# HeatpumpMonitor.net
KiCad netlist of a schematic drawn in EAGLE
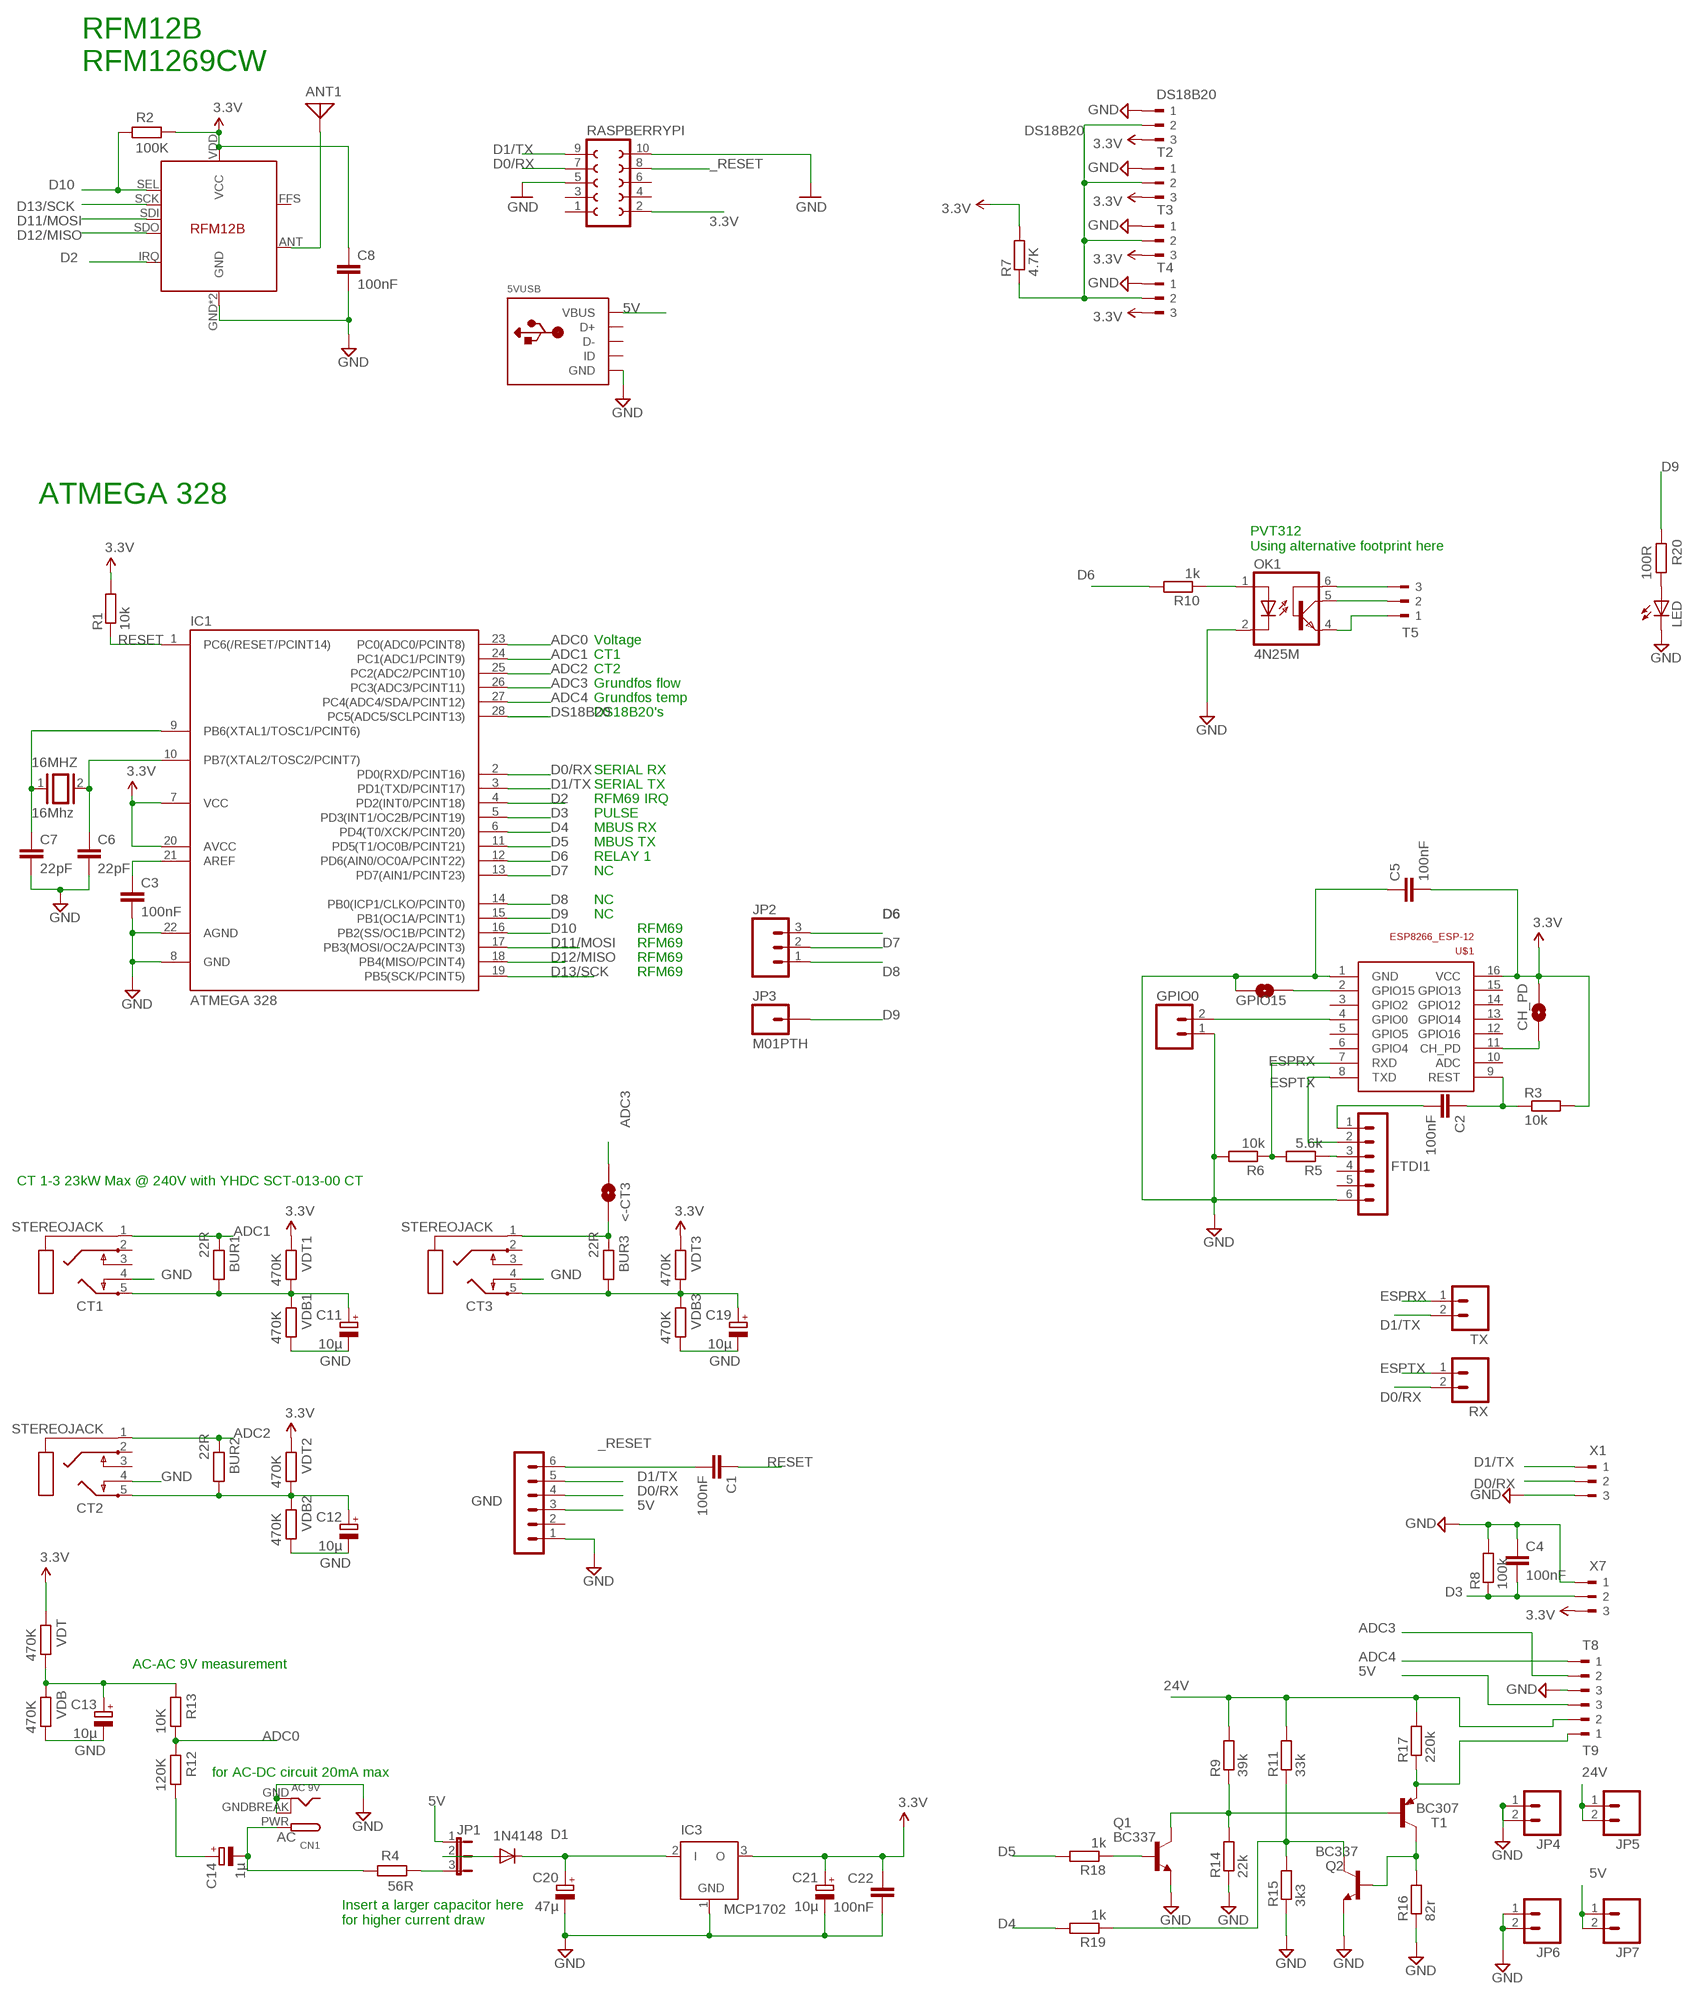
[diagram p0: schematic, sheet 1]

(export (version "E")
  (design (tool "Eeschema 10.0.6"))
  (components
    (comp (ref "5VUSB")
      (value "USBMOLEX")
      (footprint "eagle-import:USB-MINIB-THM-MOLEX")
      (libsource (lib "eagle-import") (part "USBMOLEX"))
    )
    (comp (ref "16MHZ")
      (value "16Mhz")
      (footprint "eagle-import:QS")
      (libsource (lib "eagle-import") (part "XTAL/S"))
    )
    (comp (ref "<-CT3")
      (value "SOLDERJUMPERNO")
      (footprint "eagle-import:SJ_2S-NO")
      (libsource (lib "eagle-import") (part "SOLDERJUMPERNO"))
    )
    (comp (ref "ANT1")
      (value "ANTENNA")
      (footprint "eagle-import:PAD-01")
      (libsource (lib "eagle-import") (part "ANTENNA"))
    )
    (comp (ref "BUR1")
      (value "22R")
      (footprint "eagle-import:0204_7")
      (libsource (lib "eagle-import") (part "R-EU_0204/7"))
    )
    (comp (ref "BUR2")
      (value "22R")
      (footprint "eagle-import:0204_7")
      (libsource (lib "eagle-import") (part "R-EU_0204/7"))
    )
    (comp (ref "BUR3")
      (value "22R")
      (footprint "eagle-import:0204_7")
      (libsource (lib "eagle-import") (part "R-EU_0204/7"))
    )
    (comp (ref "C1")
      (value "100nF")
      (footprint "eagle-import:C025-024X044")
      (libsource (lib "eagle-import") (part "C-EU025-024X044"))
    )
    (comp (ref "C2")
      (value "100nF")
      (footprint "eagle-import:C025-024X044")
      (libsource (lib "eagle-import") (part "C-EU025-024X044"))
    )
    (comp (ref "C3")
      (value "100nF")
      (footprint "eagle-import:C025-024X044")
      (libsource (lib "eagle-import") (part "C-EU025-024X044"))
    )
    (comp (ref "C4")
      (value "100nF")
      (footprint "eagle-import:C025-024X044")
      (libsource (lib "eagle-import") (part "C-EU025-024X044"))
    )
    (comp (ref "C5")
      (value "100nF")
      (footprint "eagle-import:C025-024X044")
      (libsource (lib "eagle-import") (part "C-EU025-024X044"))
    )
    (comp (ref "C6")
      (value "22pF")
      (footprint "eagle-import:C2.5-2")
      (libsource (lib "eagle-import") (part "C2.5/2"))
    )
    (comp (ref "C7")
      (value "22pF")
      (footprint "eagle-import:C2.5-2")
      (libsource (lib "eagle-import") (part "C2.5/2"))
    )
    (comp (ref "C8")
      (value "100nF")
      (footprint "eagle-import:C025-024X044")
      (libsource (lib "eagle-import") (part "C-EU025-024X044"))
    )
    (comp (ref "C11")
      (value "10µ")
      (footprint "eagle-import:E1,8-4")
      (libsource (lib "eagle-import") (part "CPOL-EUE1.8-4"))
    )
    (comp (ref "C12")
      (value "10µ")
      (footprint "eagle-import:E1,8-4")
      (libsource (lib "eagle-import") (part "CPOL-EUE1.8-4"))
    )
    (comp (ref "C13")
      (value "10µ")
      (footprint "eagle-import:E1,8-4")
      (libsource (lib "eagle-import") (part "CPOL-EUE1.8-4"))
    )
    (comp (ref "C14")
      (value "1µ")
      (footprint "eagle-import:E1,8-4")
      (libsource (lib "eagle-import") (part "CPOL-EUE1.8-4"))
    )
    (comp (ref "C19")
      (value "10µ")
      (footprint "eagle-import:E1,8-4")
      (libsource (lib "eagle-import") (part "CPOL-EUE1.8-4"))
    )
    (comp (ref "C20")
      (value "47µ")
      (footprint "eagle-import:E1,8-4")
      (libsource (lib "eagle-import") (part "CPOL-EUE1.8-4"))
    )
    (comp (ref "C21")
      (value "10µ")
      (footprint "eagle-import:E1,8-4")
      (libsource (lib "eagle-import") (part "CPOL-EUE1.8-4"))
    )
    (comp (ref "C22")
      (value "100nF")
      (footprint "eagle-import:C025-024X044")
      (libsource (lib "eagle-import") (part "C-EU025-024X044"))
    )
    (comp (ref "CH_PD")
      (value "SOLDERJUMPERNO")
      (footprint "eagle-import:SJ_2S-NO")
      (libsource (lib "eagle-import") (part "SOLDERJUMPERNO"))
    )
    (comp (ref "CN1")
      (value "AC 9V")
      (footprint "eagle-import:DCJACK_2MM_PTH")
      (libsource (lib "eagle-import") (part "DCBARRELPTH"))
    )
    (comp (ref "CT1")
      (value "STEREOJACK")
      (footprint "eagle-import:STX3100")
      (libsource (lib "eagle-import") (part "STEREOJACK"))
    )
    (comp (ref "CT2")
      (value "STEREOJACK")
      (footprint "eagle-import:STX3100")
      (libsource (lib "eagle-import") (part "STEREOJACK"))
    )
    (comp (ref "CT3")
      (value "STEREOJACK")
      (footprint "eagle-import:STX3100")
      (libsource (lib "eagle-import") (part "STEREOJACK"))
    )
    (comp (ref "D1")
      (value "1N4148")
      (footprint "eagle-import:DIODE-1N4148")
      (libsource (lib "eagle-import") (part "DIODE1N4148"))
    )
    (comp (ref "DS18B20")
      (value "180-3")
      (footprint "eagle-import:180-3")
      (libsource (lib "eagle-import") (part "180-3"))
    )
    (comp (ref "FTDI1")
      (value "FTDI")
      (footprint "eagle-import:MA06-1")
      (libsource (lib "eagle-import") (part "MA06-1"))
    )
    (comp (ref "GND")
      (value "FTDI")
      (footprint "eagle-import:MA06-1")
      (libsource (lib "eagle-import") (part "MA06-1"))
    )
    (comp (ref "GPIO0")
      (value "M02PTH")
      (footprint "eagle-import:1X02")
      (libsource (lib "eagle-import") (part "M02PTH"))
    )
    (comp (ref "GPIO15")
      (value "SOLDERJUMPERNO")
      (footprint "eagle-import:SJ_2S-NO")
      (libsource (lib "eagle-import") (part "SOLDERJUMPERNO"))
    )
    (comp (ref "IC1")
      (value "ATMEGA 328")
      (footprint "eagle-import:DIL28-3")
      (libsource (lib "eagle-import") (part "ATMEGA48/88/168-PU"))
    )
    (comp (ref "IC3")
      (value "MCP1702")
      (footprint "eagle-import:TO92")
      (libsource (lib "eagle-import") (part "MCP1702Z"))
    )
    (comp (ref "JP1")
      (value "JP2E")
      (footprint "eagle-import:JP2")
      (libsource (lib "eagle-import") (part "JP2E"))
    )
    (comp (ref "JP2")
      (value "M03PTH")
      (footprint "eagle-import:1X03")
      (libsource (lib "eagle-import") (part "M03PTH"))
    )
    (comp (ref "JP3")
      (value "M01PTH")
      (footprint "eagle-import:1X01")
      (libsource (lib "eagle-import") (part "M01PTH"))
    )
    (comp (ref "JP4")
      (value "M02PTH")
      (footprint "eagle-import:1X02")
      (libsource (lib "eagle-import") (part "M02PTH"))
    )
    (comp (ref "JP5")
      (value "M02PTH")
      (footprint "eagle-import:1X02")
      (libsource (lib "eagle-import") (part "M02PTH"))
    )
    (comp (ref "JP6")
      (value "M02PTH")
      (footprint "eagle-import:1X02")
      (libsource (lib "eagle-import") (part "M02PTH"))
    )
    (comp (ref "JP7")
      (value "M02PTH")
      (footprint "eagle-import:1X02")
      (libsource (lib "eagle-import") (part "M02PTH"))
    )
    (comp (ref "LED")
      (value "LED3MM")
      (footprint "eagle-import:LED3MM")
      (libsource (lib "eagle-import") (part "LED3MM"))
    )
    (comp (ref "OK1")
      (value "4N25M")
      (footprint "eagle-import:DIL06")
      (fields (field (name "MPN") "4N25-M"))
      (libsource (lib "eagle-import") (part "4N?M25"))
    )
    (comp (ref "Q1")
      (value "BC337")
      (footprint "eagle-import:TO92")
      (libsource (lib "eagle-import") (part "BC337"))
    )
    (comp (ref "Q2")
      (value "BC337")
      (footprint "eagle-import:TO92")
      (libsource (lib "eagle-import") (part "BC337"))
    )
    (comp (ref "R1")
      (value "10k")
      (footprint "eagle-import:0204_7")
      (libsource (lib "eagle-import") (part "resistor_R-EU_0204/7"))
    )
    (comp (ref "R2")
      (value "100K")
      (footprint "eagle-import:0204_7")
      (libsource (lib "eagle-import") (part "R-EU_0204/7"))
    )
    (comp (ref "R3")
      (value "10k")
      (footprint "eagle-import:0204_7")
      (libsource (lib "eagle-import") (part "R-EU_0204/7"))
    )
    (comp (ref "R4")
      (value "56R")
      (footprint "eagle-import:0204_7")
      (libsource (lib "eagle-import") (part "R-EU_0204/7"))
    )
    (comp (ref "R5")
      (value "5.6k")
      (footprint "eagle-import:0204_7")
      (libsource (lib "eagle-import") (part "R-EU_0204/7"))
    )
    (comp (ref "R6")
      (value "10k")
      (footprint "eagle-import:0204_7")
      (libsource (lib "eagle-import") (part "R-EU_0204/7"))
    )
    (comp (ref "R7")
      (value "4.7K")
      (footprint "eagle-import:0204_7")
      (libsource (lib "eagle-import") (part "resistor_R-EU_0204/7"))
    )
    (comp (ref "R8")
      (value "100k")
      (footprint "eagle-import:0207_2V")
      (libsource (lib "eagle-import") (part "R-EU_0207/2V"))
    )
    (comp (ref "R9")
      (value "39k")
      (footprint "eagle-import:0204_7")
      (libsource (lib "eagle-import") (part "resistor_R-EU_0204/7"))
    )
    (comp (ref "R10")
      (value "1k")
      (footprint "eagle-import:0204_7")
      (libsource (lib "eagle-import") (part "R-EU_0204/7"))
    )
    (comp (ref "R11")
      (value "33k")
      (footprint "eagle-import:0204_7")
      (libsource (lib "eagle-import") (part "resistor_R-EU_0204/7"))
    )
    (comp (ref "R12")
      (value "120K")
      (footprint "eagle-import:0204_7")
      (libsource (lib "eagle-import") (part "R-EU_0204/7"))
    )
    (comp (ref "R13")
      (value "10K")
      (footprint "eagle-import:0204_7")
      (libsource (lib "eagle-import") (part "R-EU_0204/7"))
    )
    (comp (ref "R14")
      (value "22k")
      (footprint "eagle-import:0204_7")
      (libsource (lib "eagle-import") (part "resistor_R-EU_0204/7"))
    )
    (comp (ref "R15")
      (value "3k3")
      (footprint "eagle-import:0204_7")
      (libsource (lib "eagle-import") (part "resistor_R-EU_0204/7"))
    )
    (comp (ref "R16")
      (value "82r")
      (footprint "eagle-import:0204_7")
      (libsource (lib "eagle-import") (part "resistor_R-EU_0204/7"))
    )
    (comp (ref "R17")
      (value "220k")
      (footprint "eagle-import:0204_7")
      (libsource (lib "eagle-import") (part "resistor_R-EU_0204/7"))
    )
    (comp (ref "R18")
      (value "1k")
      (footprint "eagle-import:0204_7")
      (libsource (lib "eagle-import") (part "resistor_R-EU_0204/7"))
    )
    (comp (ref "R19")
      (value "1k")
      (footprint "eagle-import:0204_7")
      (libsource (lib "eagle-import") (part "resistor_R-EU_0204/7"))
    )
    (comp (ref "R20")
      (value "100R")
      (footprint "eagle-import:0204_7")
      (libsource (lib "eagle-import") (part "R-EU_0204/7"))
    )
    (comp (ref "RASPBERRYPI")
      (value "FE05-2")
      (footprint "eagle-import:FE05-2")
      (libsource (lib "eagle-import") (part "FE05-2"))
    )
    (comp (ref "RX")
      (value "M02PTH")
      (footprint "eagle-import:1X02")
      (libsource (lib "eagle-import") (part "M02PTH"))
    )
    (comp (ref "T1")
      (value "BC307")
      (footprint "eagle-import:TO92")
      (libsource (lib "eagle-import") (part "BC307"))
    )
    (comp (ref "T2")
      (value "180-3")
      (footprint "eagle-import:180-3")
      (libsource (lib "eagle-import") (part "180-3"))
    )
    (comp (ref "T3")
      (value "180-3")
      (footprint "eagle-import:180-3")
      (libsource (lib "eagle-import") (part "180-3"))
    )
    (comp (ref "T4")
      (value "180-3")
      (footprint "eagle-import:180-3")
      (libsource (lib "eagle-import") (part "180-3"))
    )
    (comp (ref "T5")
      (value "180-3")
      (footprint "eagle-import:180-3")
      (libsource (lib "eagle-import") (part "180-3"))
    )
    (comp (ref "T8")
      (value "180-3")
      (footprint "eagle-import:180-3")
      (libsource (lib "eagle-import") (part "180-3"))
    )
    (comp (ref "T9")
      (value "180-3")
      (footprint "eagle-import:180-3")
      (libsource (lib "eagle-import") (part "180-3"))
    )
    (comp (ref "TX")
      (value "M02PTH")
      (footprint "eagle-import:1X02")
      (libsource (lib "eagle-import") (part "M02PTH"))
    )
    (comp (ref "U$1")
      (value "ESP8266_ESP-12")
      (footprint "eagle-import:ESP8266-ESP12")
      (libsource (lib "eagle-import") (part "ESP8266_ESP-12"))
    )
    (comp (ref "U$14")
      (value "RFM12B")
      (footprint "eagle-import:RFM12B")
      (libsource (lib "eagle-import") (part "RFM12B"))
    )
    (comp (ref "VDB")
      (value "470K")
      (footprint "eagle-import:0204_7")
      (libsource (lib "eagle-import") (part "R-EU_0204/7"))
    )
    (comp (ref "VDB1")
      (value "470K")
      (footprint "eagle-import:0204_7")
      (libsource (lib "eagle-import") (part "R-EU_0204/7"))
    )
    (comp (ref "VDB2")
      (value "470K")
      (footprint "eagle-import:0204_7")
      (libsource (lib "eagle-import") (part "R-EU_0204/7"))
    )
    (comp (ref "VDB3")
      (value "470K")
      (footprint "eagle-import:0204_7")
      (libsource (lib "eagle-import") (part "R-EU_0204/7"))
    )
    (comp (ref "VDT")
      (value "470K")
      (footprint "eagle-import:0204_7")
      (libsource (lib "eagle-import") (part "R-EU_0204/7"))
    )
    (comp (ref "VDT1")
      (value "470K")
      (footprint "eagle-import:0204_7")
      (libsource (lib "eagle-import") (part "R-EU_0204/7"))
    )
    (comp (ref "VDT2")
      (value "470K")
      (footprint "eagle-import:0204_7")
      (libsource (lib "eagle-import") (part "R-EU_0204/7"))
    )
    (comp (ref "VDT3")
      (value "470K")
      (footprint "eagle-import:0204_7")
      (libsource (lib "eagle-import") (part "R-EU_0204/7"))
    )
    (comp (ref "X1")
      (value "180-3")
      (footprint "eagle-import:180-3")
      (libsource (lib "eagle-import") (part "180-3"))
    )
    (comp (ref "X7")
      (value "180-3")
      (footprint "eagle-import:180-3")
      (libsource (lib "eagle-import") (part "180-3"))
    )
  )
  (nets
    (net (code "1") (name "/5V") (class "Default")
      (node (ref "5VUSB") (pin "VBUS") (pinfunction "VBUS_VBUS") (pintype "power_in"))
      (node (ref "GND") (pin "3") (pinfunction "3_3") (pintype "passive"))
      (node (ref "JP1") (pin "1") (pinfunction "1_1") (pintype "passive"))
      (node (ref "JP7") (pin "1") (pinfunction "1_1") (pintype "passive"))
      (node (ref "JP7") (pin "2") (pinfunction "2_2") (pintype "passive"))
      (node (ref "T9") (pin "3") (pinfunction "3_3") (pintype "passive"))
    )
    (net (code "2") (name "/24V") (class "Default")
      (node (ref "JP5") (pin "1") (pinfunction "1_1") (pintype "passive"))
      (node (ref "JP5") (pin "2") (pinfunction "2_2") (pintype "passive"))
      (node (ref "R11") (pin "2") (pinfunction "2_2") (pintype "passive"))
      (node (ref "R17") (pin "2") (pinfunction "2_2") (pintype "passive"))
      (node (ref "R9") (pin "2") (pinfunction "2_2") (pintype "passive"))
      (node (ref "T9") (pin "2") (pinfunction "2_2") (pintype "passive"))
    )
    (net (code "3") (name "/AC") (class "Default")
      (node (ref "C14") (pin "-") (pinfunction "-_-") (pintype "passive"))
      (node (ref "CN1") (pin "PWR") (pinfunction "PWR_PWR") (pintype "power_in"))
      (node (ref "R4") (pin "2") (pinfunction "2_2") (pintype "passive"))
    )
    (net (code "4") (name "/ADC0") (class "Default")
      (node (ref "IC1") (pin "23") (pinfunction "PC0(ADC0/PCINT8)_23") (pintype "bidirectional"))
      (node (ref "R12") (pin "2") (pinfunction "2_2") (pintype "passive"))
      (node (ref "R13") (pin "1") (pinfunction "1_1") (pintype "passive"))
    )
    (net (code "5") (name "/ADC1") (class "Default")
      (node (ref "BUR1") (pin "2") (pinfunction "2_2") (pintype "passive"))
      (node (ref "CT1") (pin "1") (pinfunction "1_1") (pintype "passive"))
      (node (ref "IC1") (pin "24") (pinfunction "PC1(ADC1/PCINT9)_24") (pintype "bidirectional"))
    )
    (net (code "6") (name "/ADC2") (class "Default")
      (node (ref "BUR2") (pin "2") (pinfunction "2_2") (pintype "passive"))
      (node (ref "CT2") (pin "1") (pinfunction "1_1") (pintype "passive"))
      (node (ref "IC1") (pin "25") (pinfunction "PC2(ADC2/PCINT10)_25") (pintype "bidirectional"))
    )
    (net (code "7") (name "/ADC3") (class "Default")
      (node (ref "<-CT3") (pin "2") (pinfunction "2_2") (pintype "passive"))
      (node (ref "IC1") (pin "26") (pinfunction "PC3(ADC3/PCINT11)_26") (pintype "bidirectional"))
      (node (ref "T8") (pin "2") (pinfunction "2_2") (pintype "passive"))
    )
    (net (code "8") (name "/ADC4") (class "Default")
      (node (ref "IC1") (pin "27") (pinfunction "PC4(ADC4/SDA/PCINT12)_27") (pintype "bidirectional"))
      (node (ref "T8") (pin "1") (pinfunction "1_1") (pintype "passive"))
    )
    (net (code "9") (name "/D0{slash}RX") (class "Default")
      (node (ref "GND") (pin "4") (pinfunction "4_4") (pintype "passive"))
      (node (ref "IC1") (pin "2") (pinfunction "PD0(RXD/PCINT16)_2") (pintype "bidirectional"))
      (node (ref "RASPBERRYPI") (pin "7") (pinfunction "7_7") (pintype "passive"))
      (node (ref "RX") (pin "2") (pinfunction "2_2") (pintype "passive"))
      (node (ref "X1") (pin "2") (pinfunction "2_2") (pintype "passive"))
    )
    (net (code "10") (name "/D1{slash}TX") (class "Default")
      (node (ref "GND") (pin "5") (pinfunction "5_5") (pintype "passive"))
      (node (ref "IC1") (pin "3") (pinfunction "PD1(TXD/PCINT17)_3") (pintype "bidirectional"))
      (node (ref "RASPBERRYPI") (pin "9") (pinfunction "9_9") (pintype "passive"))
      (node (ref "TX") (pin "2") (pinfunction "2_2") (pintype "passive"))
      (node (ref "X1") (pin "1") (pinfunction "1_1") (pintype "passive"))
    )
    (net (code "11") (name "/D2") (class "Default")
      (node (ref "IC1") (pin "4") (pinfunction "PD2(INT0/PCINT18)_4") (pintype "bidirectional"))
      (node (ref "U$14") (pin "IRQ") (pinfunction "IRQ_IRQ") (pintype "open_collector"))
    )
    (net (code "12") (name "/D3") (class "Default")
      (node (ref "C4") (pin "2") (pinfunction "2_2") (pintype "passive"))
      (node (ref "IC1") (pin "5") (pinfunction "PD3(INT1/OC2B/PCINT19)_5") (pintype "bidirectional"))
      (node (ref "R8") (pin "1") (pinfunction "1_1") (pintype "passive"))
      (node (ref "X7") (pin "2") (pinfunction "2_2") (pintype "passive"))
    )
    (net (code "13") (name "/D4") (class "Default")
      (node (ref "IC1") (pin "6") (pinfunction "PD4(T0/XCK/PCINT20)_6") (pintype "bidirectional"))
      (node (ref "R19") (pin "2") (pinfunction "2_2") (pintype "passive"))
    )
    (net (code "14") (name "/D5") (class "Default")
      (node (ref "IC1") (pin "11") (pinfunction "PD5(T1/OC0B/PCINT21)_11") (pintype "bidirectional"))
      (node (ref "R18") (pin "2") (pinfunction "2_2") (pintype "passive"))
    )
    (net (code "15") (name "/D6") (class "Default")
      (node (ref "IC1") (pin "12") (pinfunction "PD6(AIN0/OC0A/PCINT22)_12") (pintype "bidirectional"))
      (node (ref "JP2") (pin "3") (pinfunction "3_3") (pintype "passive"))
      (node (ref "R10") (pin "2") (pinfunction "2_2") (pintype "passive"))
    )
    (net (code "16") (name "/D7") (class "Default")
      (node (ref "IC1") (pin "13") (pinfunction "PD7(AIN1/PCINT23)_13") (pintype "bidirectional"))
      (node (ref "JP2") (pin "2") (pinfunction "2_2") (pintype "passive"))
    )
    (net (code "17") (name "/D8") (class "Default")
      (node (ref "IC1") (pin "14") (pinfunction "PB0(ICP1/CLKO/PCINT0)_14") (pintype "bidirectional"))
      (node (ref "JP2") (pin "1") (pinfunction "1_1") (pintype "passive"))
    )
    (net (code "18") (name "/D9") (class "Default")
      (node (ref "IC1") (pin "15") (pinfunction "PB1(OC1A/PCINT1)_15") (pintype "bidirectional"))
      (node (ref "JP3") (pin "1") (pinfunction "1_1") (pintype "passive"))
      (node (ref "R20") (pin "2") (pinfunction "2_2") (pintype "passive"))
    )
    (net (code "19") (name "/D10") (class "Default")
      (node (ref "IC1") (pin "16") (pinfunction "PB2(SS/OC1B/PCINT2)_16") (pintype "bidirectional"))
      (node (ref "R2") (pin "2") (pinfunction "2_2") (pintype "passive"))
      (node (ref "U$14") (pin "SEL") (pinfunction "SEL_SEL") (pintype "input"))
    )
    (net (code "20") (name "/D11{slash}MOSI") (class "Default")
      (node (ref "IC1") (pin "17") (pinfunction "PB3(MOSI/OC2A/PCINT3)_17") (pintype "bidirectional"))
      (node (ref "U$14") (pin "SDI") (pinfunction "SDI_SDI") (pintype "input"))
    )
    (net (code "21") (name "/D12{slash}MISO") (class "Default")
      (node (ref "IC1") (pin "18") (pinfunction "PB4(MISO/PCINT4)_18") (pintype "bidirectional"))
      (node (ref "U$14") (pin "SDO") (pinfunction "SDO_SDO") (pintype "output"))
    )
    (net (code "22") (name "/D13{slash}SCK") (class "Default")
      (node (ref "IC1") (pin "19") (pinfunction "PB5(SCK/PCINT5)_19") (pintype "bidirectional"))
      (node (ref "U$14") (pin "SCK") (pinfunction "SCK_SCK") (pintype "input"))
    )
    (net (code "23") (name "/DS18B20") (class "Default")
      (node (ref "DS18B20") (pin "2") (pinfunction "2_2") (pintype "passive"))
      (node (ref "IC1") (pin "28") (pinfunction "PC5(ADC5/SCLPCINT13)_28") (pintype "bidirectional"))
      (node (ref "R7") (pin "1") (pinfunction "1_1") (pintype "passive"))
      (node (ref "T2") (pin "2") (pinfunction "2_2") (pintype "passive"))
      (node (ref "T3") (pin "2") (pinfunction "2_2") (pintype "passive"))
      (node (ref "T4") (pin "2") (pinfunction "2_2") (pintype "passive"))
    )
    (net (code "24") (name "/ESPRX") (class "Default")
      (node (ref "R5") (pin "2") (pinfunction "2_2") (pintype "passive"))
      (node (ref "R6") (pin "1") (pinfunction "1_1") (pintype "passive"))
      (node (ref "TX") (pin "1") (pinfunction "1_1") (pintype "passive"))
      (node (ref "U$1") (pin "7") (pinfunction "RXD_7") (pintype "bidirectional"))
    )
    (net (code "25") (name "/ESPTX") (class "Default")
      (node (ref "FTDI1") (pin "2") (pinfunction "2_2") (pintype "passive"))
      (node (ref "RX") (pin "1") (pinfunction "1_1") (pintype "passive"))
      (node (ref "U$1") (pin "8") (pinfunction "TXD_8") (pintype "bidirectional"))
    )
    (net (code "26") (name "/RESET") (class "Default")
      (node (ref "C1") (pin "1") (pinfunction "1_1") (pintype "passive"))
      (node (ref "IC1") (pin "1") (pinfunction "PC6(/RESET/PCINT14)_1") (pintype "bidirectional"))
      (node (ref "R1") (pin "1") (pinfunction "1_1") (pintype "passive"))
    )
    (net (code "27") (name "/_RESET") (class "Default")
      (node (ref "C1") (pin "2") (pinfunction "2_2") (pintype "passive"))
      (node (ref "GND") (pin "6") (pinfunction "6_6") (pintype "passive"))
      (node (ref "RASPBERRYPI") (pin "8") (pinfunction "8_8") (pintype "passive"))
    )
    (net (code "28") (name "3.3V") (class "Default")
      (node (ref "C21") (pin "+") (pinfunction "+_+") (pintype "passive"))
      (node (ref "C22") (pin "1") (pinfunction "1_1") (pintype "passive"))
      (node (ref "C5") (pin "2") (pinfunction "2_2") (pintype "passive"))
      (node (ref "C8") (pin "1") (pinfunction "1_1") (pintype "passive"))
      (node (ref "CH_PD") (pin "1") (pinfunction "1_1") (pintype "passive"))
      (node (ref "DS18B20") (pin "3") (pinfunction "3_3") (pintype "passive"))
      (node (ref "IC1") (pin "20") (pinfunction "AVCC_20") (pintype "passive"))
      (node (ref "IC1") (pin "7") (pinfunction "VCC_7") (pintype "power_in"))
      (node (ref "IC3") (pin "3") (pinfunction "O_3") (pintype "input"))
      (node (ref "R1") (pin "2") (pinfunction "2_2") (pintype "passive"))
      (node (ref "R2") (pin "1") (pinfunction "1_1") (pintype "passive"))
      (node (ref "R3") (pin "2") (pinfunction "2_2") (pintype "passive"))
      (node (ref "R7") (pin "2") (pinfunction "2_2") (pintype "passive"))
      (node (ref "RASPBERRYPI") (pin "2") (pinfunction "2_2") (pintype "passive"))
      (node (ref "T2") (pin "3") (pinfunction "3_3") (pintype "passive"))
      (node (ref "T3") (pin "3") (pinfunction "3_3") (pintype "passive"))
      (node (ref "T4") (pin "3") (pinfunction "3_3") (pintype "passive"))
      (node (ref "U$1") (pin "16") (pinfunction "VCC_16") (pintype "bidirectional"))
      (node (ref "U$14") (pin "VDD") (pinfunction "VCC_VDD") (pintype "power_in"))
      (node (ref "VDT") (pin "2") (pinfunction "2_2") (pintype "passive"))
      (node (ref "VDT1") (pin "2") (pinfunction "2_2") (pintype "passive"))
      (node (ref "VDT2") (pin "2") (pinfunction "2_2") (pintype "passive"))
      (node (ref "VDT3") (pin "2") (pinfunction "2_2") (pintype "passive"))
      (node (ref "X7") (pin "3") (pinfunction "3_3") (pintype "passive"))
    )
    (net (code "29") (name "GND") (class "Default")
      (node (ref "5VUSB") (pin "GND") (pinfunction "GND_GND") (pintype "power_in"))
      (node (ref "C11") (pin "-") (pinfunction "-_-") (pintype "passive"))
      (node (ref "C12") (pin "-") (pinfunction "-_-") (pintype "passive"))
      (node (ref "C13") (pin "-") (pinfunction "-_-") (pintype "passive"))
      (node (ref "C19") (pin "-") (pinfunction "-_-") (pintype "passive"))
      (node (ref "C20") (pin "-") (pinfunction "-_-") (pintype "passive"))
      (node (ref "C21") (pin "-") (pinfunction "-_-") (pintype "passive"))
      (node (ref "C22") (pin "2") (pinfunction "2_2") (pintype "passive"))
      (node (ref "C3") (pin "2") (pinfunction "2_2") (pintype "passive"))
      (node (ref "C4") (pin "1") (pinfunction "1_1") (pintype "passive"))
      (node (ref "C5") (pin "1") (pinfunction "1_1") (pintype "passive"))
      (node (ref "C6") (pin "2") (pinfunction "2_2") (pintype "passive"))
      (node (ref "C7") (pin "2") (pinfunction "2_2") (pintype "passive"))
      (node (ref "C8") (pin "2") (pinfunction "2_2") (pintype "passive"))
      (node (ref "CN1") (pin "GND") (pinfunction "GND_GND") (pintype "power_in"))
      (node (ref "CN1") (pin "GNDBREAK") (pinfunction "GNDBREAK_GNDBREAK") (pintype "power_in"))
      (node (ref "CT1") (pin "4") (pinfunction "4_4") (pintype "passive"))
      (node (ref "CT2") (pin "4") (pinfunction "4_4") (pintype "passive"))
      (node (ref "CT3") (pin "4") (pinfunction "4_4") (pintype "passive"))
      (node (ref "DS18B20") (pin "1") (pinfunction "1_1") (pintype "passive"))
      (node (ref "FTDI1") (pin "6") (pinfunction "6_6") (pintype "passive"))
      (node (ref "GND") (pin "1") (pinfunction "1_1") (pintype "passive"))
      (node (ref "GPIO0") (pin "1") (pinfunction "1_1") (pintype "passive"))
      (node (ref "GPIO15") (pin "2") (pinfunction "2_2") (pintype "passive"))
      (node (ref "IC1") (pin "22") (pinfunction "AGND_22") (pintype "power_in"))
      (node (ref "IC1") (pin "8") (pinfunction "GND_8") (pintype "power_in"))
      (node (ref "IC3") (pin "1") (pinfunction "GND_1") (pintype "power_in"))
      (node (ref "JP4") (pin "1") (pinfunction "1_1") (pintype "passive"))
      (node (ref "JP4") (pin "2") (pinfunction "2_2") (pintype "passive"))
      (node (ref "JP6") (pin "1") (pinfunction "1_1") (pintype "passive"))
      (node (ref "JP6") (pin "2") (pinfunction "2_2") (pintype "passive"))
      (node (ref "LED") (pin "K") (pinfunction "C_K") (pintype "passive"))
      (node (ref "OK1") (pin "2") (pinfunction "C_2") (pintype "passive"))
      (node (ref "Q1") (pin "1") (pinfunction "E_1") (pintype "passive"))
      (node (ref "Q2") (pin "1") (pinfunction "E_1") (pintype "passive"))
      (node (ref "R14") (pin "1") (pinfunction "1_1") (pintype "passive"))
      (node (ref "R15") (pin "1") (pinfunction "1_1") (pintype "passive"))
      (node (ref "R16") (pin "1") (pinfunction "1_1") (pintype "passive"))
      (node (ref "R6") (pin "2") (pinfunction "2_2") (pintype "passive"))
      (node (ref "R8") (pin "2") (pinfunction "2_2") (pintype "passive"))
      (node (ref "RASPBERRYPI") (pin "10") (pinfunction "10_10") (pintype "passive"))
      (node (ref "RASPBERRYPI") (pin "5") (pinfunction "5_5") (pintype "passive"))
      (node (ref "T2") (pin "1") (pinfunction "1_1") (pintype "passive"))
      (node (ref "T3") (pin "1") (pinfunction "1_1") (pintype "passive"))
      (node (ref "T4") (pin "1") (pinfunction "1_1") (pintype "passive"))
      (node (ref "T8") (pin "3") (pinfunction "3_3") (pintype "passive"))
      (node (ref "U$1") (pin "1") (pinfunction "GND_1") (pintype "bidirectional"))
      (node (ref "U$14") (pin "GND") (pinfunction "GND_GND") (pintype "power_in"))
      (node (ref "U$14") (pin "P$12") (pinfunction "GND_P$12") (pintype "power_in"))
      (node (ref "VDB") (pin "1") (pinfunction "1_1") (pintype "passive"))
      (node (ref "VDB1") (pin "1") (pinfunction "1_1") (pintype "passive"))
      (node (ref "VDB2") (pin "1") (pinfunction "1_1") (pintype "passive"))
      (node (ref "VDB3") (pin "1") (pinfunction "1_1") (pintype "passive"))
      (node (ref "X1") (pin "3") (pinfunction "3_3") (pintype "passive"))
      (node (ref "X7") (pin "1") (pinfunction "1_1") (pintype "passive"))
    )
    (net (code "30") (name "Net-(<-CT3-Pad1)") (class "Default")
      (node (ref "<-CT3") (pin "1") (pinfunction "1_1") (pintype "passive"))
      (node (ref "BUR3") (pin "2") (pinfunction "2_2") (pintype "passive"))
      (node (ref "CT3") (pin "1") (pinfunction "1_1") (pintype "passive"))
    )
    (net (code "31") (name "Net-(ANT1-Pad1)") (class "Default")
      (node (ref "ANT1") (pin "1") (pinfunction "1_1") (pintype "output"))
      (node (ref "U$14") (pin "ANT") (pinfunction "ANT_ANT") (pintype "passive"))
    )
    (net (code "32") (name "Net-(BUR1-Pad1)") (class "Default")
      (node (ref "BUR1") (pin "1") (pinfunction "1_1") (pintype "passive"))
      (node (ref "C11") (pin "+") (pinfunction "+_+") (pintype "passive"))
      (node (ref "CT1") (pin "5") (pinfunction "5_5") (pintype "passive"))
      (node (ref "VDB1") (pin "2") (pinfunction "2_2") (pintype "passive"))
      (node (ref "VDT1") (pin "1") (pinfunction "1_1") (pintype "passive"))
    )
    (net (code "33") (name "Net-(BUR2-Pad1)") (class "Default")
      (node (ref "BUR2") (pin "1") (pinfunction "1_1") (pintype "passive"))
      (node (ref "C12") (pin "+") (pinfunction "+_+") (pintype "passive"))
      (node (ref "CT2") (pin "5") (pinfunction "5_5") (pintype "passive"))
      (node (ref "VDB2") (pin "2") (pinfunction "2_2") (pintype "passive"))
      (node (ref "VDT2") (pin "1") (pinfunction "1_1") (pintype "passive"))
    )
    (net (code "34") (name "Net-(BUR3-Pad1)") (class "Default")
      (node (ref "BUR3") (pin "1") (pinfunction "1_1") (pintype "passive"))
      (node (ref "C19") (pin "+") (pinfunction "+_+") (pintype "passive"))
      (node (ref "CT3") (pin "5") (pinfunction "5_5") (pintype "passive"))
      (node (ref "VDB3") (pin "2") (pinfunction "2_2") (pintype "passive"))
      (node (ref "VDT3") (pin "1") (pinfunction "1_1") (pintype "passive"))
    )
    (net (code "35") (name "Net-(C2-Pad2)") (class "Default")
      (node (ref "C2") (pin "2") (pinfunction "2_2") (pintype "passive"))
      (node (ref "FTDI1") (pin "1") (pinfunction "1_1") (pintype "passive"))
    )
    (net (code "36") (name "Net-(C13-Pad+)") (class "Default")
      (node (ref "C13") (pin "+") (pinfunction "+_+") (pintype "passive"))
      (node (ref "R13") (pin "2") (pinfunction "2_2") (pintype "passive"))
      (node (ref "VDB") (pin "2") (pinfunction "2_2") (pintype "passive"))
      (node (ref "VDT") (pin "1") (pinfunction "1_1") (pintype "passive"))
    )
    (net (code "37") (name "Net-(C14-Pad+)") (class "Default")
      (node (ref "C14") (pin "+") (pinfunction "+_+") (pintype "passive"))
      (node (ref "R12") (pin "1") (pinfunction "1_1") (pintype "passive"))
    )
    (net (code "38") (name "Net-(D1-PadA)") (class "Default")
      (node (ref "D1") (pin "A") (pinfunction "A_A") (pintype "passive"))
      (node (ref "JP1") (pin "2") (pinfunction "2_2") (pintype "passive"))
    )
    (net (code "39") (name "Net-(FTDI1-Pad3)") (class "Default")
      (node (ref "FTDI1") (pin "3") (pinfunction "3_3") (pintype "passive"))
      (node (ref "R5") (pin "1") (pinfunction "1_1") (pintype "passive"))
    )
    (net (code "40") (name "Net-(IC1-AREF)") (class "Default")
      (node (ref "C3") (pin "1") (pinfunction "1_1") (pintype "passive"))
      (node (ref "IC1") (pin "21") (pinfunction "AREF_21") (pintype "passive"))
    )
    (net (code "41") (name "Net-(IC1-PB6(XTAL1{slash}TOSC1{slash}PCINT6))") (class "Default")
      (node (ref "16MHZ") (pin "1") (pinfunction "1_1") (pintype "passive"))
      (node (ref "C7") (pin "1") (pinfunction "1_1") (pintype "passive"))
      (node (ref "IC1") (pin "9") (pinfunction "PB6(XTAL1/TOSC1/PCINT6)_9") (pintype "bidirectional"))
    )
    (net (code "42") (name "Net-(IC1-PB7(XTAL2{slash}TOSC2{slash}PCINT7))") (class "Default")
      (node (ref "16MHZ") (pin "2") (pinfunction "2_2") (pintype "passive"))
      (node (ref "C6") (pin "1") (pinfunction "1_1") (pintype "passive"))
      (node (ref "IC1") (pin "10") (pinfunction "PB7(XTAL2/TOSC2/PCINT7)_10") (pintype "bidirectional"))
    )
    (net (code "43") (name "Net-(IC3-I)") (class "Default")
      (node (ref "C20") (pin "+") (pinfunction "+_+") (pintype "passive"))
      (node (ref "D1") (pin "C") (pinfunction "C_C") (pintype "passive"))
      (node (ref "IC3") (pin "2") (pinfunction "I_2") (pintype "input"))
    )
    (net (code "44") (name "Net-(JP1-Pad3)") (class "Default")
      (node (ref "JP1") (pin "3") (pinfunction "3_3") (pintype "passive"))
      (node (ref "R4") (pin "1") (pinfunction "1_1") (pintype "passive"))
    )
    (net (code "45") (name "Net-(LED-PadA)") (class "Default")
      (node (ref "LED") (pin "A") (pinfunction "A_A") (pintype "passive"))
      (node (ref "R20") (pin "1") (pinfunction "1_1") (pintype "passive"))
    )
    (net (code "46") (name "Net-(OK1-A)") (class "Default")
      (node (ref "OK1") (pin "1") (pinfunction "A_1") (pintype "passive"))
      (node (ref "R10") (pin "1") (pinfunction "1_1") (pintype "passive"))
    )
    (net (code "47") (name "Net-(OK1-BAS)") (class "Default")
      (node (ref "OK1") (pin "6") (pinfunction "BAS_6") (pintype "passive"))
      (node (ref "T5") (pin "3") (pinfunction "3_3") (pintype "passive"))
    )
    (net (code "48") (name "Net-(OK1-COL)") (class "Default")
      (node (ref "OK1") (pin "5") (pinfunction "COL_5") (pintype "passive"))
      (node (ref "T5") (pin "2") (pinfunction "2_2") (pintype "passive"))
    )
    (net (code "49") (name "Net-(OK1-EMI)") (class "Default")
      (node (ref "OK1") (pin "4") (pinfunction "EMI_4") (pintype "passive"))
      (node (ref "T5") (pin "1") (pinfunction "1_1") (pintype "passive"))
    )
    (net (code "50") (name "Net-(Q1-B)") (class "Default")
      (node (ref "Q1") (pin "2") (pinfunction "B_2") (pintype "passive"))
      (node (ref "R18") (pin "1") (pinfunction "1_1") (pintype "passive"))
    )
    (net (code "51") (name "Net-(Q1-C)") (class "Default")
      (node (ref "Q1") (pin "3") (pinfunction "C_3") (pintype "passive"))
      (node (ref "R14") (pin "2") (pinfunction "2_2") (pintype "passive"))
      (node (ref "R9") (pin "1") (pinfunction "1_1") (pintype "passive"))
      (node (ref "T1") (pin "2") (pinfunction "B_2") (pintype "passive"))
    )
    (net (code "52") (name "Net-(Q2-B)") (class "Default")
      (node (ref "Q2") (pin "2") (pinfunction "B_2") (pintype "passive"))
      (node (ref "R16") (pin "2") (pinfunction "2_2") (pintype "passive"))
      (node (ref "T1") (pin "3") (pinfunction "C_3") (pintype "passive"))
    )
    (net (code "53") (name "Net-(Q2-C)") (class "Default")
      (node (ref "Q2") (pin "3") (pinfunction "C_3") (pintype "passive"))
      (node (ref "R11") (pin "1") (pinfunction "1_1") (pintype "passive"))
      (node (ref "R15") (pin "2") (pinfunction "2_2") (pintype "passive"))
      (node (ref "R19") (pin "1") (pinfunction "1_1") (pintype "passive"))
    )
    (net (code "54") (name "Net-(T1-E)") (class "Default")
      (node (ref "R17") (pin "1") (pinfunction "1_1") (pintype "passive"))
      (node (ref "T1") (pin "1") (pinfunction "E_1") (pintype "passive"))
      (node (ref "T9") (pin "1") (pinfunction "1_1") (pintype "passive"))
    )
    (net (code "55") (name "Net-(U$1-CH_PD)") (class "Default")
      (node (ref "CH_PD") (pin "2") (pinfunction "2_2") (pintype "passive"))
      (node (ref "U$1") (pin "11") (pinfunction "CH_PD_11") (pintype "bidirectional"))
    )
    (net (code "56") (name "Net-(U$1-GPIO0)") (class "Default")
      (node (ref "GPIO0") (pin "2") (pinfunction "2_2") (pintype "passive"))
      (node (ref "U$1") (pin "4") (pinfunction "GPIO0_4") (pintype "bidirectional"))
    )
    (net (code "57") (name "Net-(U$1-GPIO15)") (class "Default")
      (node (ref "GPIO15") (pin "1") (pinfunction "1_1") (pintype "passive"))
      (node (ref "U$1") (pin "2") (pinfunction "GPIO15_2") (pintype "bidirectional"))
    )
    (net (code "58") (name "Net-(U$1-REST)") (class "Default")
      (node (ref "C2") (pin "1") (pinfunction "1_1") (pintype "passive"))
      (node (ref "R3") (pin "1") (pinfunction "1_1") (pintype "passive"))
      (node (ref "U$1") (pin "9") (pinfunction "REST_9") (pintype "bidirectional"))
    )
    (net (code "59") (name "unconnected-(5VUSB-PadD+)") (class "Default")
      (node (ref "5VUSB") (pin "D+") (pinfunction "D+_D+") (pintype "bidirectional"))
    )
    (net (code "60") (name "unconnected-(5VUSB-PadD-)") (class "Default")
      (node (ref "5VUSB") (pin "D-") (pinfunction "D-_D-") (pintype "bidirectional"))
    )
    (net (code "61") (name "unconnected-(5VUSB-PadID)") (class "Default")
      (node (ref "5VUSB") (pin "ID") (pinfunction "ID_ID") (pintype "bidirectional"))
    )
    (net (code "62") (name "unconnected-(CT1-Pad2)") (class "Default")
      (node (ref "CT1") (pin "2") (pinfunction "2_2") (pintype "passive"))
    )
    (net (code "63") (name "unconnected-(CT1-Pad3)") (class "Default")
      (node (ref "CT1") (pin "3") (pinfunction "3_3") (pintype "passive"))
    )
    (net (code "64") (name "unconnected-(CT2-Pad2)") (class "Default")
      (node (ref "CT2") (pin "2") (pinfunction "2_2") (pintype "passive"))
    )
    (net (code "65") (name "unconnected-(CT2-Pad3)") (class "Default")
      (node (ref "CT2") (pin "3") (pinfunction "3_3") (pintype "passive"))
    )
    (net (code "66") (name "unconnected-(CT3-Pad2)") (class "Default")
      (node (ref "CT3") (pin "2") (pinfunction "2_2") (pintype "passive"))
    )
    (net (code "67") (name "unconnected-(CT3-Pad3)") (class "Default")
      (node (ref "CT3") (pin "3") (pinfunction "3_3") (pintype "passive"))
    )
    (net (code "68") (name "unconnected-(FTDI1-Pad4)") (class "Default")
      (node (ref "FTDI1") (pin "4") (pinfunction "4_4") (pintype "passive"))
    )
    (net (code "69") (name "unconnected-(FTDI1-Pad5)") (class "Default")
      (node (ref "FTDI1") (pin "5") (pinfunction "5_5") (pintype "passive"))
    )
    (net (code "70") (name "unconnected-(GND-Pad2)") (class "Default")
      (node (ref "GND") (pin "2") (pinfunction "2_2") (pintype "passive"))
    )
    (net (code "71") (name "unconnected-(RASPBERRYPI-Pad1)") (class "Default")
      (node (ref "RASPBERRYPI") (pin "1") (pinfunction "1_1") (pintype "passive"))
    )
    (net (code "72") (name "unconnected-(RASPBERRYPI-Pad3)") (class "Default")
      (node (ref "RASPBERRYPI") (pin "3") (pinfunction "3_3") (pintype "passive"))
    )
    (net (code "73") (name "unconnected-(RASPBERRYPI-Pad4)") (class "Default")
      (node (ref "RASPBERRYPI") (pin "4") (pinfunction "4_4") (pintype "passive"))
    )
    (net (code "74") (name "unconnected-(RASPBERRYPI-Pad6)") (class "Default")
      (node (ref "RASPBERRYPI") (pin "6") (pinfunction "6_6") (pintype "passive"))
    )
    (net (code "75") (name "unconnected-(U$1-ADC-Pad10)") (class "Default")
      (node (ref "U$1") (pin "10") (pinfunction "ADC_10") (pintype "bidirectional"))
    )
    (net (code "76") (name "unconnected-(U$1-GPIO2-Pad3)") (class "Default")
      (node (ref "U$1") (pin "3") (pinfunction "GPIO2_3") (pintype "bidirectional"))
    )
    (net (code "77") (name "unconnected-(U$1-GPIO4-Pad6)") (class "Default")
      (node (ref "U$1") (pin "6") (pinfunction "GPIO4_6") (pintype "bidirectional"))
    )
    (net (code "78") (name "unconnected-(U$1-GPIO5-Pad5)") (class "Default")
      (node (ref "U$1") (pin "5") (pinfunction "GPIO5_5") (pintype "bidirectional"))
    )
    (net (code "79") (name "unconnected-(U$1-GPIO12-Pad14)") (class "Default")
      (node (ref "U$1") (pin "14") (pinfunction "GPIO12_14") (pintype "bidirectional"))
    )
    (net (code "80") (name "unconnected-(U$1-GPIO13-Pad15)") (class "Default")
      (node (ref "U$1") (pin "15") (pinfunction "GPIO13_15") (pintype "bidirectional"))
    )
    (net (code "81") (name "unconnected-(U$1-GPIO14-Pad13)") (class "Default")
      (node (ref "U$1") (pin "13") (pinfunction "GPIO14_13") (pintype "bidirectional"))
    )
    (net (code "82") (name "unconnected-(U$1-GPIO16-Pad12)") (class "Default")
      (node (ref "U$1") (pin "12") (pinfunction "GPIO16_12") (pintype "bidirectional"))
    )
    (net (code "83") (name "unconnected-(U$14-PadFFS)") (class "Default")
      (node (ref "U$14") (pin "FFS") (pinfunction "FFS_FFS") (pintype "bidirectional"))
    )
  )
)
